# Power_Monitoring_TPS3803.net
KiCad netlist of a schematic drawn in Altium Designer
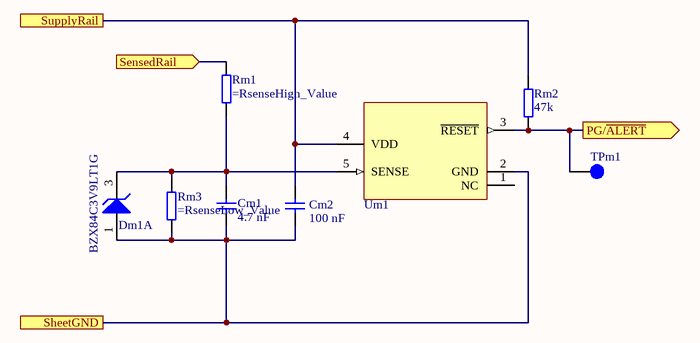
[diagram p0: Power_Monitoring_TPS3803.SchDoc]

(export (version "E")
  (design (tool "Eeschema 10.0.6"))
  (components
    (comp (ref "Cm1")
      (value "4.7 nF")
      (footprint "C_0603_TE")
      (description "50V 4.7nF C0G ±5% 0603 Multilayer Ceramic Capacitors MLCC")
      (fields
        (field (name "TOLERANCE") "5%")
        (field (name "MANUFACTURER PART NUMBER") "GRM1885C1H472JA01D")
        (field (name "CREATED FROM") "MGeier")
      )
      (libsource (lib "user") (part "CAP-NP"))
    )
    (comp (ref "Cm2")
      (value "100 nF")
      (footprint "C_0603_TE")
      (description "Generic capacitor")
      (fields
        (field (name "MANUFACTURER PART NUMBER") "UZgen_C_0603_100nF_50V_X7R")
        (field (name "MANUFACTURER") "UZgen")
        (field (name "CREATED FROM") "AGeiger")
      )
      (libsource (lib "user") (part "CAP-NP"))
    )
    (comp (ref "Dm1")
      (value "BZX84C3V9LT1G")
      (footprint "SOT-23-3_ONSC")
      (description "Zener Diode, 3.9 V, 0.25 W, 5 %")
      (fields
        (field (name "MANUFACTURER") "onsemi")
        (field (name "LCSC PART NUMBER") "C94414")
        (field (name "CREATED FROM") "FRosner")
      )
      (libsource (lib "user") (part "Zener_Diode_generic3pin1A"))
    )
    (comp (ref "Rm1")
      (value "~")
      (footprint "R_0603_TE")
      (description "Generic resistor (parametric)")
      (fields
        (field (name "MANUFACTURER PART NUMBER") "UZgen_R_0603_")
        (field (name "MANUFACTURER") "UZgen")
        (field (name "CREATED FROM") "UZgenTool")
      )
      (libsource (lib "user") (part "RES"))
    )
    (comp (ref "Rm2")
      (value "47k")
      (footprint "R_0603_TE")
      (description "Generic resistor")
      (fields
        (field (name "MANUFACTURER PART NUMBER") "UZgen_R_0603_47k")
        (field (name "MANUFACTURER") "UZgen")
        (field (name "CREATED FROM") "UZgenTool")
      )
      (libsource (lib "user") (part "RES"))
    )
    (comp (ref "Rm3")
      (value "~")
      (footprint "R_0603_TE")
      (description "Generic resistor (parametric)")
      (fields
        (field (name "MANUFACTURER PART NUMBER") "UZgen_R_0603_")
        (field (name "MANUFACTURER") "UZgen")
        (field (name "CREATED FROM") "UZgenTool")
      )
      (libsource (lib "user") (part "RES"))
    )
    (comp (ref "TPm1")
      (value "Testpoint 1mm")
      (footprint "TP_1mm")
      (fields
        (field (name "MANUFACTURER PART NUMBER") "NULL")
        (field (name "CREATED") "2018_06_25_AGeiger")
        (field (name "CREATED FROM") "AGeiger")
      )
      (libsource (lib "user") (part "TP_1mm"))
    )
    (comp (ref "Um1")
      (value "TPS3803-01QDCKRQ1")
      (footprint "FP-DCK0005A-IPC_B")
      (description "Supervisory Circuits Auto Cat Dual Vltg Detectors")
      (fields
        (field (name "MANUFACTURER") "Texas Instruments")
        (field (name "LCSC PART NUMBER") "C129371")
        (field (name "CREATED FROM") "FRosner")
      )
      (libsource (lib "user") (part "TPS3803"))
    )
  )
  (nets
    (net (code "1") (name "/PG{slash}~{ALERT}") (class "Default")
      (node (ref "Rm2") (pin "1") (pinfunction "1_1") (pintype "passive"))
      (node (ref "TPm1") (pin "1") (pintype "passive"))
      (node (ref "Um1") (pin "3") (pinfunction "~{RESET}_3") (pintype "output"))
    )
    (net (code "2") (name "/SensedRail") (class "Default")
      (node (ref "Rm1") (pin "2") (pinfunction "2_2") (pintype "passive"))
    )
    (net (code "3") (name "/SheetGND") (class "Default")
      (node (ref "Cm1") (pin "2") (pinfunction "2_2") (pintype "passive"))
      (node (ref "Cm2") (pin "1") (pinfunction "1_1") (pintype "passive"))
      (node (ref "Dm1") (pin "1") (pinfunction "A_1") (pintype "passive"))
      (node (ref "Rm3") (pin "1") (pinfunction "1_1") (pintype "passive"))
      (node (ref "Um1") (pin "2") (pinfunction "GND_2") (pintype "passive"))
    )
    (net (code "4") (name "/SupplyRail") (class "Default")
      (node (ref "Cm2") (pin "2") (pinfunction "2_2") (pintype "passive"))
      (node (ref "Rm2") (pin "2") (pinfunction "2_2") (pintype "passive"))
      (node (ref "Um1") (pin "4") (pinfunction "VDD_4") (pintype "power_in"))
    )
    (net (code "5") (name "Net-(Dm1A-K)") (class "Default")
      (node (ref "Cm1") (pin "1") (pinfunction "1_1") (pintype "passive"))
      (node (ref "Dm1") (pin "3") (pinfunction "K_3") (pintype "passive"))
      (node (ref "Rm1") (pin "1") (pinfunction "1_1") (pintype "passive"))
      (node (ref "Rm3") (pin "2") (pinfunction "2_2") (pintype "passive"))
      (node (ref "Um1") (pin "5") (pinfunction "SENSE_5") (pintype "input"))
    )
    (net (code "6") (name "unconnected-(Um1-NC-Pad1)") (class "Default")
      (node (ref "Um1") (pin "1") (pinfunction "NC_1") (pintype "passive"))
    )
  )
)
